# BareBones_Arduino_With_Multiplexer.net
KiCad netlist of a schematic drawn in EAGLE
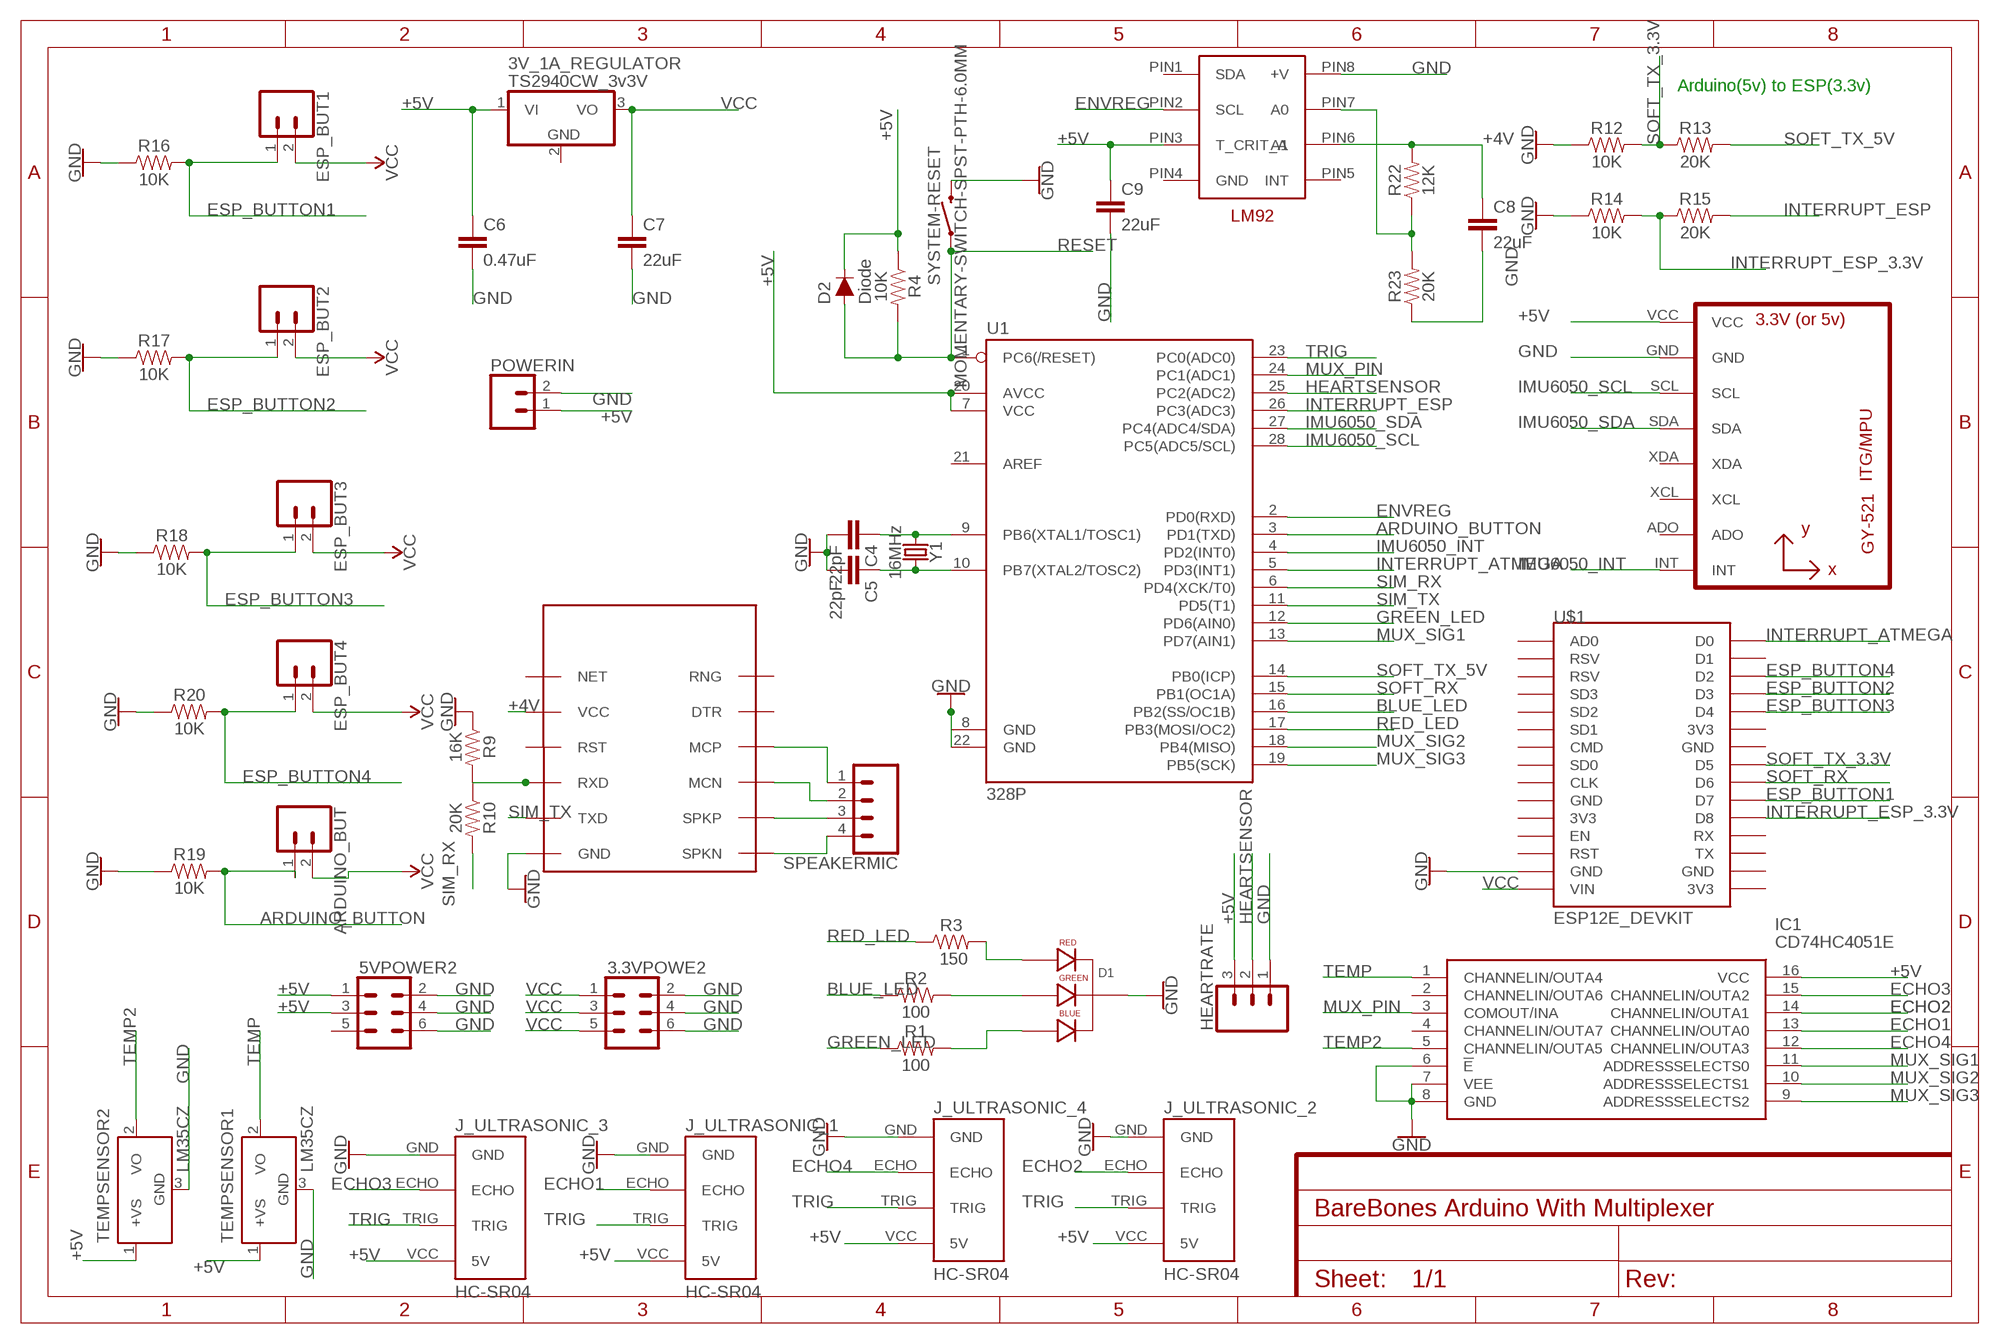
[diagram p0: schematic, sheet 1]

(export (version "E")
  (design (tool "Eeschema 10.0.6"))
  (components
    (comp (ref "3.3VPOWE2")
      (value "CONN_03X2FEMALE")
      (footprint "eagle-import:2X3")
      (libsource (lib "eagle-import") (part "CONN_03X2FEMALE"))
    )
    (comp (ref "3V_1A_REGULATOR")
      (value "TS2940CW_3v3V")
      (footprint "eagle-import:SOT223")
      (libsource (lib "eagle-import") (part "MCP1703DB"))
    )
    (comp (ref "5VPOWER2")
      (value "CONN_03X2FEMALE")
      (footprint "eagle-import:2X3")
      (libsource (lib "eagle-import") (part "CONN_03X2FEMALE"))
    )
    (comp (ref "ARDUINO_BUT")
      (value "CONN_02")
      (footprint "eagle-import:1X02")
      (libsource (lib "eagle-import") (part "CONN_02"))
    )
    (comp (ref "C4")
      (value "22pF")
      (footprint "eagle-import:CAP-PTH-2.54")
      (libsource (lib "eagle-import") (part "22PF-PTH-2.54MM-200V-5%"))
    )
    (comp (ref "C5")
      (value "22pF")
      (footprint "eagle-import:CAP-PTH-2.54")
      (libsource (lib "eagle-import") (part "22PF-PTH-2.54MM-200V-5%"))
    )
    (comp (ref "C6")
      (value "0.47uF")
      (footprint "eagle-import:CAP-PTH-SMALL-KIT")
      (libsource (lib "eagle-import") (part "0.1UF-KIT-EZ-50V-20%"))
    )
    (comp (ref "C7")
      (value "22uF")
      (footprint "eagle-import:CAP-PTH-SMALL-KIT")
      (libsource (lib "eagle-import") (part "0.1UF-KIT-EZ-50V-20%"))
    )
    (comp (ref "C8")
      (value "22uF")
      (footprint "eagle-import:CAP-PTH-SMALL-KIT")
      (libsource (lib "eagle-import") (part "0.1UF-KIT-EZ-50V-20%"))
    )
    (comp (ref "C9")
      (value "22uF")
      (footprint "eagle-import:CAP-PTH-SMALL-KIT")
      (libsource (lib "eagle-import") (part "0.1UF-KIT-EZ-50V-20%"))
    )
    (comp (ref "D1")
      (value "LED-RGB-CC-THRUDIFFUSE")
      (footprint "eagle-import:LED-RGB-THRU")
      (libsource (lib "eagle-import") (part "LED-RGB-CC-THRUDIFFUSE"))
    )
    (comp (ref "D2")
      (value "Diode")
      (footprint "eagle-import:DIODE-1N4148")
      (libsource (lib "eagle-import") (part "DIODE-1N4148"))
    )
    (comp (ref "ESP_BUT1")
      (value "CONN_02")
      (footprint "eagle-import:1X02")
      (libsource (lib "eagle-import") (part "CONN_02"))
    )
    (comp (ref "ESP_BUT2")
      (value "CONN_02")
      (footprint "eagle-import:1X02")
      (libsource (lib "eagle-import") (part "CONN_02"))
    )
    (comp (ref "ESP_BUT3")
      (value "CONN_02")
      (footprint "eagle-import:1X02")
      (libsource (lib "eagle-import") (part "CONN_02"))
    )
    (comp (ref "ESP_BUT4")
      (value "CONN_02")
      (footprint "eagle-import:1X02")
      (libsource (lib "eagle-import") (part "CONN_02"))
    )
    (comp (ref "HEARTRATE")
      (value "CONN_03")
      (footprint "eagle-import:1X03")
      (libsource (lib "eagle-import") (part "CONN_03"))
    )
    (comp (ref "IC1")
      (value "CD74HC4051E")
      (footprint "eagle-import:DIP794W53P254L1930H508Q16N")
      (fields (field (name "RS_PART_NUMBER") "2508240054"))
      (libsource (lib "eagle-import") (part "CD74HC4051E"))
    )
    (comp (ref "J_ULTRASONIC_1")
      (value "HC-SR04")
      (footprint "eagle-import:HC-SR04_FOOTPRINT")
      (libsource (lib "eagle-import") (part "HC-SR04"))
    )
    (comp (ref "J_ULTRASONIC_2")
      (value "HC-SR04")
      (footprint "eagle-import:HC-SR04_FOOTPRINT")
      (libsource (lib "eagle-import") (part "HC-SR04"))
    )
    (comp (ref "J_ULTRASONIC_3")
      (value "HC-SR04")
      (footprint "eagle-import:HC-SR04_FOOTPRINT")
      (libsource (lib "eagle-import") (part "HC-SR04"))
    )
    (comp (ref "J_ULTRASONIC_4")
      (value "HC-SR04")
      (footprint "eagle-import:HC-SR04_FOOTPRINT")
      (libsource (lib "eagle-import") (part "HC-SR04"))
    )
    (comp (ref "POWERIN")
      (value "CONN_025MM")
      (footprint "eagle-import:SCREWTERMINAL-5MM-2")
      (libsource (lib "eagle-import") (part "CONN_025MM"))
    )
    (comp (ref "R1")
      (value "100")
      (footprint "eagle-import:AXIAL-0.3")
      (libsource (lib "eagle-import") (part "100OHM-HORIZ-1/4W-1%"))
    )
    (comp (ref "R2")
      (value "100")
      (footprint "eagle-import:AXIAL-0.3")
      (libsource (lib "eagle-import") (part "100OHM-HORIZ-1/4W-1%"))
    )
    (comp (ref "R3")
      (value "150")
      (footprint "eagle-import:AXIAL-0.3")
      (libsource (lib "eagle-import") (part "RESISTORAXIAL-0.3"))
    )
    (comp (ref "R4")
      (value "10K")
      (footprint "eagle-import:AXIAL-0.3")
      (libsource (lib "eagle-import") (part "100OHM-HORIZ-1/4W-1%"))
    )
    (comp (ref "R9")
      (value "16K")
      (footprint "eagle-import:AXIAL-0.3")
      (libsource (lib "eagle-import") (part "100OHM-HORIZ-1/4W-1%"))
    )
    (comp (ref "R10")
      (value "20K")
      (footprint "eagle-import:AXIAL-0.3")
      (libsource (lib "eagle-import") (part "100OHM-HORIZ-1/4W-1%"))
    )
    (comp (ref "R12")
      (value "10K")
      (footprint "eagle-import:AXIAL-0.3")
      (libsource (lib "eagle-import") (part "100OHM-HORIZ-1/4W-1%"))
    )
    (comp (ref "R13")
      (value "20K")
      (footprint "eagle-import:AXIAL-0.3")
      (libsource (lib "eagle-import") (part "100OHM-HORIZ-1/4W-1%"))
    )
    (comp (ref "R14")
      (value "10K")
      (footprint "eagle-import:AXIAL-0.3")
      (libsource (lib "eagle-import") (part "100OHM-HORIZ-1/4W-1%"))
    )
    (comp (ref "R15")
      (value "20K")
      (footprint "eagle-import:AXIAL-0.3")
      (libsource (lib "eagle-import") (part "100OHM-HORIZ-1/4W-1%"))
    )
    (comp (ref "R16")
      (value "10K")
      (footprint "eagle-import:AXIAL-0.3")
      (libsource (lib "eagle-import") (part "100OHM-HORIZ-1/4W-1%"))
    )
    (comp (ref "R17")
      (value "10K")
      (footprint "eagle-import:AXIAL-0.3")
      (libsource (lib "eagle-import") (part "100OHM-HORIZ-1/4W-1%"))
    )
    (comp (ref "R18")
      (value "10K")
      (footprint "eagle-import:AXIAL-0.3")
      (libsource (lib "eagle-import") (part "100OHM-HORIZ-1/4W-1%"))
    )
    (comp (ref "R19")
      (value "10K")
      (footprint "eagle-import:AXIAL-0.3")
      (libsource (lib "eagle-import") (part "100OHM-HORIZ-1/4W-1%"))
    )
    (comp (ref "R20")
      (value "10K")
      (footprint "eagle-import:AXIAL-0.3")
      (libsource (lib "eagle-import") (part "100OHM-HORIZ-1/4W-1%"))
    )
    (comp (ref "R22")
      (value "12K")
      (footprint "eagle-import:AXIAL-0.3")
      (libsource (lib "eagle-import") (part "100OHM-HORIZ-1/4W-1%"))
    )
    (comp (ref "R23")
      (value "20K")
      (footprint "eagle-import:AXIAL-0.3")
      (libsource (lib "eagle-import") (part "100OHM-HORIZ-1/4W-1%"))
    )
    (comp (ref "SPEAKERMIC")
      (value "CONN_04")
      (footprint "eagle-import:1X04")
      (libsource (lib "eagle-import") (part "CONN_04"))
    )
    (comp (ref "SYSTEM-RESET")
      (value "MOMENTARY-SWITCH-SPST-PTH-6.0MM")
      (footprint "eagle-import:TACTILE_SWITCH_PTH_6.0MM")
      (libsource (lib "eagle-import") (part "MOMENTARY-SWITCH-SPST-PTH-6.0MM"))
    )
    (comp (ref "TEMPSENSOR1")
      (value "LM35CZ")
      (footprint "eagle-import:TO92")
      (libsource (lib "eagle-import") (part "LM35CZ"))
    )
    (comp (ref "TEMPSENSOR2")
      (value "LM35CZ")
      (footprint "eagle-import:TO92")
      (libsource (lib "eagle-import") (part "LM35CZ"))
    )
    (comp (ref "U$1")
      (value "ESP12E_DEVKIT")
      (footprint "eagle-import:ESP12E_DEVKIT")
      (libsource (lib "eagle-import") (part "ESP12E_DEVKIT"))
    )
    (comp (ref "U$4")
      (value "SIM800L")
      (footprint "eagle-import:SIM-CORE")
      (libsource (lib "eagle-import") (part "SIM800L"))
    )
    (comp (ref "U1")
      (value "328P")
      (footprint "eagle-import:DIP28")
      (libsource (lib "eagle-import") (part "ATMEGA328P_PDIP"))
    )
    (comp (ref "U2")
      (value "GY-521MPU6050")
      (footprint "eagle-import:GY-521")
      (libsource (lib "eagle-import") (part "GY-521MPU6050"))
    )
    (comp (ref "VREG")
      (value "LM92")
      (footprint "eagle-import:SOP-8")
      (fields (field (name "SPICEPREFIX") "X"))
      (libsource (lib "eagle-import") (part "LM92"))
    )
    (comp (ref "Y1")
      (value "16MHz")
      (footprint "eagle-import:HC49US")
      (libsource (lib "eagle-import") (part "CRYSTAL-16MHZPTH-HC49US"))
    )
  )
  (nets
    (net (code "1") (name "/+4V") (class "Default")
      (node (ref "C8") (pin "1") (pinfunction "1_1") (pintype "passive"))
      (node (ref "R22") (pin "P$2") (pinfunction "2_P$2") (pintype "passive"))
      (node (ref "U$4") (pin "VCC") (pinfunction "VCC_VCC") (pintype "bidirectional"))
      (node (ref "VREG") (pin "PIN6") (pinfunction "A1_PIN6") (pintype "bidirectional"))
    )
    (net (code "2") (name "/+5V") (class "Default")
      (node (ref "3V_1A_REGULATOR") (pin "1") (pinfunction "VI_1") (pintype "input"))
      (node (ref "5VPOWER2") (pin "1") (pinfunction "1_1") (pintype "bidirectional"))
      (node (ref "5VPOWER2") (pin "3") (pinfunction "3_3") (pintype "bidirectional"))
      (node (ref "C6") (pin "1") (pinfunction "1_1") (pintype "passive"))
      (node (ref "C9") (pin "1") (pinfunction "1_1") (pintype "passive"))
      (node (ref "D2") (pin "C") (pinfunction "C_C") (pintype "passive"))
      (node (ref "HEARTRATE") (pin "3") (pinfunction "3_3") (pintype "passive"))
      (node (ref "IC1") (pin "16") (pinfunction "VCC_16") (pintype "input"))
      (node (ref "J_ULTRASONIC_1") (pin "VCC") (pinfunction "5V_VCC") (pintype "bidirectional"))
      (node (ref "J_ULTRASONIC_2") (pin "VCC") (pinfunction "5V_VCC") (pintype "bidirectional"))
      (node (ref "J_ULTRASONIC_3") (pin "VCC") (pinfunction "5V_VCC") (pintype "bidirectional"))
      (node (ref "J_ULTRASONIC_4") (pin "VCC") (pinfunction "5V_VCC") (pintype "bidirectional"))
      (node (ref "POWERIN") (pin "1") (pinfunction "1_1") (pintype "passive"))
      (node (ref "R4") (pin "P$1") (pinfunction "1_P$1") (pintype "passive"))
      (node (ref "TEMPSENSOR1") (pin "1") (pinfunction "+VS_1") (pintype "input"))
      (node (ref "TEMPSENSOR2") (pin "1") (pinfunction "+VS_1") (pintype "input"))
      (node (ref "U1") (pin "20") (pinfunction "AVCC_20") (pintype "bidirectional"))
      (node (ref "U1") (pin "7") (pinfunction "VCC_7") (pintype "bidirectional"))
      (node (ref "U2") (pin "VCC") (pinfunction "VCC_VCC") (pintype "bidirectional"))
      (node (ref "VREG") (pin "PIN3") (pinfunction "T_CRIT_A_PIN3") (pintype "bidirectional"))
    )
    (net (code "3") (name "/ARDUINO_BUTTON") (class "Default")
      (node (ref "ARDUINO_BUT") (pin "1") (pinfunction "1_1") (pintype "passive"))
      (node (ref "R19") (pin "P$2") (pinfunction "2_P$2") (pintype "passive"))
      (node (ref "U1") (pin "3") (pinfunction "PD1(TXD)_3") (pintype "bidirectional"))
    )
    (net (code "4") (name "/BLUE_LED") (class "Default")
      (node (ref "R2") (pin "P$1") (pinfunction "1_P$1") (pintype "passive"))
      (node (ref "U1") (pin "16") (pinfunction "PB2(SS/OC1B)_16") (pintype "bidirectional"))
    )
    (net (code "5") (name "/ECHO1") (class "Default")
      (node (ref "IC1") (pin "13") (pinfunction "CHANNELIN/OUTA0_13") (pintype "input"))
      (node (ref "J_ULTRASONIC_1") (pin "ECHO") (pinfunction "ECHO_ECHO") (pintype "bidirectional"))
    )
    (net (code "6") (name "/ECHO2") (class "Default")
      (node (ref "IC1") (pin "14") (pinfunction "CHANNELIN/OUTA1_14") (pintype "input"))
      (node (ref "J_ULTRASONIC_2") (pin "ECHO") (pinfunction "ECHO_ECHO") (pintype "bidirectional"))
    )
    (net (code "7") (name "/ECHO3") (class "Default")
      (node (ref "IC1") (pin "15") (pinfunction "CHANNELIN/OUTA2_15") (pintype "input"))
      (node (ref "J_ULTRASONIC_3") (pin "ECHO") (pinfunction "ECHO_ECHO") (pintype "bidirectional"))
    )
    (net (code "8") (name "/ECHO4") (class "Default")
      (node (ref "IC1") (pin "12") (pinfunction "CHANNELIN/OUTA3_12") (pintype "input"))
      (node (ref "J_ULTRASONIC_4") (pin "ECHO") (pinfunction "ECHO_ECHO") (pintype "bidirectional"))
    )
    (net (code "9") (name "/ENVREG") (class "Default")
      (node (ref "U1") (pin "2") (pinfunction "PD0(RXD)_2") (pintype "bidirectional"))
      (node (ref "VREG") (pin "PIN2") (pinfunction "SCL_PIN2") (pintype "bidirectional"))
    )
    (net (code "10") (name "/ESP_BUTTON1") (class "Default")
      (node (ref "ESP_BUT1") (pin "1") (pinfunction "1_1") (pintype "passive"))
      (node (ref "R16") (pin "P$2") (pinfunction "2_P$2") (pintype "passive"))
      (node (ref "U$1") (pin "D7") (pinfunction "D7_D7") (pintype "bidirectional"))
    )
    (net (code "11") (name "/ESP_BUTTON2") (class "Default")
      (node (ref "ESP_BUT2") (pin "1") (pinfunction "1_1") (pintype "passive"))
      (node (ref "R17") (pin "P$2") (pinfunction "2_P$2") (pintype "passive"))
      (node (ref "U$1") (pin "D3") (pinfunction "D3_D3") (pintype "bidirectional"))
    )
    (net (code "12") (name "/ESP_BUTTON3") (class "Default")
      (node (ref "ESP_BUT3") (pin "1") (pinfunction "1_1") (pintype "passive"))
      (node (ref "R18") (pin "P$2") (pinfunction "2_P$2") (pintype "passive"))
      (node (ref "U$1") (pin "D4") (pinfunction "D4_D4") (pintype "bidirectional"))
    )
    (net (code "13") (name "/ESP_BUTTON4") (class "Default")
      (node (ref "ESP_BUT4") (pin "1") (pinfunction "1_1") (pintype "passive"))
      (node (ref "R20") (pin "P$2") (pinfunction "2_P$2") (pintype "passive"))
      (node (ref "U$1") (pin "D2") (pinfunction "D2_D2") (pintype "bidirectional"))
    )
    (net (code "14") (name "/GREEN_LED") (class "Default")
      (node (ref "R1") (pin "P$1") (pinfunction "1_P$1") (pintype "passive"))
      (node (ref "U1") (pin "12") (pinfunction "PD6(AIN0)_12") (pintype "bidirectional"))
    )
    (net (code "15") (name "/HEARTSENSOR") (class "Default")
      (node (ref "HEARTRATE") (pin "2") (pinfunction "2_2") (pintype "passive"))
      (node (ref "U1") (pin "25") (pinfunction "PC2(ADC2)_25") (pintype "bidirectional"))
    )
    (net (code "16") (name "/IMU6050_INT") (class "Default")
      (node (ref "U1") (pin "4") (pinfunction "PD2(INT0)_4") (pintype "bidirectional"))
      (node (ref "U2") (pin "INT") (pinfunction "INT_INT") (pintype "bidirectional"))
    )
    (net (code "17") (name "/IMU6050_SCL") (class "Default")
      (node (ref "U1") (pin "28") (pinfunction "PC5(ADC5/SCL)_28") (pintype "bidirectional"))
      (node (ref "U2") (pin "SCL") (pinfunction "SCL_SCL") (pintype "bidirectional"))
    )
    (net (code "18") (name "/IMU6050_SDA") (class "Default")
      (node (ref "U1") (pin "27") (pinfunction "PC4(ADC4/SDA)_27") (pintype "bidirectional"))
      (node (ref "U2") (pin "SDA") (pinfunction "SDA_SDA") (pintype "bidirectional"))
    )
    (net (code "19") (name "/INTERRUPT_ATMEGA") (class "Default")
      (node (ref "U$1") (pin "D0") (pinfunction "D0_D0") (pintype "bidirectional"))
      (node (ref "U1") (pin "5") (pinfunction "PD3(INT1)_5") (pintype "bidirectional"))
    )
    (net (code "20") (name "/INTERRUPT_ESP") (class "Default")
      (node (ref "R15") (pin "P$2") (pinfunction "2_P$2") (pintype "passive"))
      (node (ref "U1") (pin "26") (pinfunction "PC3(ADC3)_26") (pintype "bidirectional"))
    )
    (net (code "21") (name "/INTERRUPT_ESP_3.3V") (class "Default")
      (node (ref "R14") (pin "P$2") (pinfunction "2_P$2") (pintype "passive"))
      (node (ref "R15") (pin "P$1") (pinfunction "1_P$1") (pintype "passive"))
      (node (ref "U$1") (pin "D8") (pinfunction "D8_D8") (pintype "bidirectional"))
    )
    (net (code "22") (name "/MUX_PIN") (class "Default")
      (node (ref "IC1") (pin "3") (pinfunction "COMOUT/INA_3") (pintype "input"))
      (node (ref "U1") (pin "24") (pinfunction "PC1(ADC1)_24") (pintype "bidirectional"))
    )
    (net (code "23") (name "/MUX_SIG1") (class "Default")
      (node (ref "IC1") (pin "11") (pinfunction "ADDRESSSELECTS0_11") (pintype "input"))
      (node (ref "U1") (pin "13") (pinfunction "PD7(AIN1)_13") (pintype "bidirectional"))
    )
    (net (code "24") (name "/MUX_SIG2") (class "Default")
      (node (ref "IC1") (pin "10") (pinfunction "ADDRESSSELECTS1_10") (pintype "input"))
      (node (ref "U1") (pin "18") (pinfunction "PB4(MISO)_18") (pintype "bidirectional"))
    )
    (net (code "25") (name "/MUX_SIG3") (class "Default")
      (node (ref "IC1") (pin "9") (pinfunction "ADDRESSSELECTS2_9") (pintype "input"))
      (node (ref "U1") (pin "19") (pinfunction "PB5(SCK)_19") (pintype "bidirectional"))
    )
    (net (code "26") (name "/RED_LED") (class "Default")
      (node (ref "R3") (pin "P$1") (pinfunction "1_P$1") (pintype "passive"))
      (node (ref "U1") (pin "17") (pinfunction "PB3(MOSI/OC2)_17") (pintype "bidirectional"))
    )
    (net (code "27") (name "/RESET") (class "Default")
      (node (ref "D2") (pin "A") (pinfunction "A_A") (pintype "passive"))
      (node (ref "R4") (pin "P$2") (pinfunction "2_P$2") (pintype "passive"))
      (node (ref "SYSTEM-RESET") (pin "1") (pinfunction "1_1") (pintype "passive"))
      (node (ref "U1") (pin "1") (pinfunction "PC6(/RESET)_1") (pintype "bidirectional"))
    )
    (net (code "28") (name "/SIM_RX") (class "Default")
      (node (ref "R10") (pin "P$2") (pinfunction "2_P$2") (pintype "passive"))
      (node (ref "U1") (pin "6") (pinfunction "PD4(XCK/T0)_6") (pintype "bidirectional"))
    )
    (net (code "29") (name "/SIM_TX") (class "Default")
      (node (ref "U$4") (pin "TXD") (pinfunction "TXD_TXD") (pintype "bidirectional"))
      (node (ref "U1") (pin "11") (pinfunction "PD5(T1)_11") (pintype "bidirectional"))
    )
    (net (code "30") (name "/SOFT_RX") (class "Default")
      (node (ref "U$1") (pin "D6") (pinfunction "D6_D6") (pintype "bidirectional"))
      (node (ref "U1") (pin "15") (pinfunction "PB1(OC1A)_15") (pintype "bidirectional"))
    )
    (net (code "31") (name "/SOFT_TX_3.3V") (class "Default")
      (node (ref "R12") (pin "P$2") (pinfunction "2_P$2") (pintype "passive"))
      (node (ref "R13") (pin "P$1") (pinfunction "1_P$1") (pintype "passive"))
      (node (ref "U$1") (pin "D5") (pinfunction "D5_D5") (pintype "bidirectional"))
    )
    (net (code "32") (name "/SOFT_TX_5V") (class "Default")
      (node (ref "R13") (pin "P$2") (pinfunction "2_P$2") (pintype "passive"))
      (node (ref "U1") (pin "14") (pinfunction "PB0(ICP)_14") (pintype "bidirectional"))
    )
    (net (code "33") (name "/TEMP") (class "Default")
      (node (ref "IC1") (pin "1") (pinfunction "CHANNELIN/OUTA4_1") (pintype "input"))
      (node (ref "TEMPSENSOR1") (pin "2") (pinfunction "VO_2") (pintype "input"))
    )
    (net (code "34") (name "/TEMP2") (class "Default")
      (node (ref "IC1") (pin "5") (pinfunction "CHANNELIN/OUTA5_5") (pintype "input"))
      (node (ref "TEMPSENSOR2") (pin "2") (pinfunction "VO_2") (pintype "input"))
    )
    (net (code "35") (name "/TRIG") (class "Default")
      (node (ref "J_ULTRASONIC_1") (pin "TRIG") (pinfunction "TRIG_TRIG") (pintype "bidirectional"))
      (node (ref "J_ULTRASONIC_2") (pin "TRIG") (pinfunction "TRIG_TRIG") (pintype "bidirectional"))
      (node (ref "J_ULTRASONIC_3") (pin "TRIG") (pinfunction "TRIG_TRIG") (pintype "bidirectional"))
      (node (ref "J_ULTRASONIC_4") (pin "TRIG") (pinfunction "TRIG_TRIG") (pintype "bidirectional"))
      (node (ref "U1") (pin "23") (pinfunction "PC0(ADC0)_23") (pintype "bidirectional"))
    )
    (net (code "36") (name "GND") (class "Default")
      (node (ref "3.3VPOWE2") (pin "2") (pinfunction "2_2") (pintype "bidirectional"))
      (node (ref "3.3VPOWE2") (pin "4") (pinfunction "4_4") (pintype "bidirectional"))
      (node (ref "3.3VPOWE2") (pin "6") (pinfunction "6_6") (pintype "bidirectional"))
      (node (ref "5VPOWER2") (pin "2") (pinfunction "2_2") (pintype "bidirectional"))
      (node (ref "5VPOWER2") (pin "4") (pinfunction "4_4") (pintype "bidirectional"))
      (node (ref "5VPOWER2") (pin "6") (pinfunction "6_6") (pintype "bidirectional"))
      (node (ref "C4") (pin "2") (pinfunction "2_2") (pintype "passive"))
      (node (ref "C5") (pin "2") (pinfunction "2_2") (pintype "passive"))
      (node (ref "C6") (pin "2") (pinfunction "2_2") (pintype "passive"))
      (node (ref "C7") (pin "2") (pinfunction "2_2") (pintype "passive"))
      (node (ref "C8") (pin "2") (pinfunction "2_2") (pintype "passive"))
      (node (ref "C9") (pin "2") (pinfunction "2_2") (pintype "passive"))
      (node (ref "D1") (pin "2") (pinfunction "CATHODE_2") (pintype "bidirectional"))
      (node (ref "HEARTRATE") (pin "1") (pinfunction "1_1") (pintype "passive"))
      (node (ref "IC1") (pin "6") (pinfunction "~{E}_6") (pintype "input"))
      (node (ref "IC1") (pin "7") (pinfunction "VEE_7") (pintype "input"))
      (node (ref "IC1") (pin "8") (pinfunction "GND_8") (pintype "input"))
      (node (ref "J_ULTRASONIC_1") (pin "GND") (pinfunction "GND_GND") (pintype "bidirectional"))
      (node (ref "J_ULTRASONIC_2") (pin "GND") (pinfunction "GND_GND") (pintype "bidirectional"))
      (node (ref "J_ULTRASONIC_3") (pin "GND") (pinfunction "GND_GND") (pintype "bidirectional"))
      (node (ref "J_ULTRASONIC_4") (pin "GND") (pinfunction "GND_GND") (pintype "bidirectional"))
      (node (ref "POWERIN") (pin "2") (pinfunction "2_2") (pintype "passive"))
      (node (ref "R12") (pin "P$1") (pinfunction "1_P$1") (pintype "passive"))
      (node (ref "R14") (pin "P$1") (pinfunction "1_P$1") (pintype "passive"))
      (node (ref "R16") (pin "P$1") (pinfunction "1_P$1") (pintype "passive"))
      (node (ref "R17") (pin "P$1") (pinfunction "1_P$1") (pintype "passive"))
      (node (ref "R18") (pin "P$1") (pinfunction "1_P$1") (pintype "passive"))
      (node (ref "R19") (pin "P$1") (pinfunction "1_P$1") (pintype "passive"))
      (node (ref "R20") (pin "P$1") (pinfunction "1_P$1") (pintype "passive"))
      (node (ref "R23") (pin "P$1") (pinfunction "1_P$1") (pintype "passive"))
      (node (ref "R9") (pin "P$1") (pinfunction "1_P$1") (pintype "passive"))
      (node (ref "SYSTEM-RESET") (pin "3") (pinfunction "2_3") (pintype "passive"))
      (node (ref "TEMPSENSOR1") (pin "3") (pinfunction "GND_3") (pintype "power_in"))
      (node (ref "TEMPSENSOR2") (pin "3") (pinfunction "GND_3") (pintype "power_in"))
      (node (ref "U$1") (pin "GND@1") (pinfunction "GND_GND@1") (pintype "bidirectional"))
      (node (ref "U$4") (pin "GND") (pinfunction "GND_GND") (pintype "bidirectional"))
      (node (ref "U1") (pin "22") (pinfunction "GND_22") (pintype "bidirectional"))
      (node (ref "U1") (pin "8") (pinfunction "GND_8") (pintype "bidirectional"))
      (node (ref "U2") (pin "GND") (pinfunction "GND_GND") (pintype "bidirectional"))
      (node (ref "VREG") (pin "PIN8") (pinfunction "+V_PIN8") (pintype "bidirectional"))
    )
    (net (code "37") (name "Net-(D1-BLUE_CATHODE)") (class "Default")
      (node (ref "D1") (pin "4") (pinfunction "BLUE_CATHODE_4") (pintype "bidirectional"))
      (node (ref "R1") (pin "P$2") (pinfunction "2_P$2") (pintype "passive"))
    )
    (net (code "38") (name "Net-(D1-GREEN_CATHODE)") (class "Default")
      (node (ref "D1") (pin "3") (pinfunction "GREEN_CATHODE_3") (pintype "bidirectional"))
      (node (ref "R2") (pin "P$2") (pinfunction "2_P$2") (pintype "passive"))
    )
    (net (code "39") (name "Net-(D1-RED_CATHODE)") (class "Default")
      (node (ref "D1") (pin "1") (pinfunction "RED_CATHODE_1") (pintype "bidirectional"))
      (node (ref "R3") (pin "P$2") (pinfunction "2_P$2") (pintype "passive"))
    )
    (net (code "40") (name "Net-(R10-1)") (class "Default")
      (node (ref "R10") (pin "P$1") (pinfunction "1_P$1") (pintype "passive"))
      (node (ref "R9") (pin "P$2") (pinfunction "2_P$2") (pintype "passive"))
      (node (ref "U$4") (pin "RXD") (pinfunction "RXD_RXD") (pintype "bidirectional"))
    )
    (net (code "41") (name "Net-(R22-1)") (class "Default")
      (node (ref "R22") (pin "P$1") (pinfunction "1_P$1") (pintype "passive"))
      (node (ref "R23") (pin "P$2") (pinfunction "2_P$2") (pintype "passive"))
      (node (ref "VREG") (pin "PIN7") (pinfunction "A0_PIN7") (pintype "bidirectional"))
    )
    (net (code "42") (name "Net-(SPEAKERMIC-Pad1)") (class "Default")
      (node (ref "SPEAKERMIC") (pin "1") (pinfunction "1_1") (pintype "passive"))
      (node (ref "U$4") (pin "MCP") (pinfunction "MCP_MCP") (pintype "bidirectional"))
    )
    (net (code "43") (name "Net-(SPEAKERMIC-Pad2)") (class "Default")
      (node (ref "SPEAKERMIC") (pin "2") (pinfunction "2_2") (pintype "passive"))
      (node (ref "U$4") (pin "MCN") (pinfunction "MCN_MCN") (pintype "bidirectional"))
    )
    (net (code "44") (name "Net-(SPEAKERMIC-Pad3)") (class "Default")
      (node (ref "SPEAKERMIC") (pin "3") (pinfunction "3_3") (pintype "passive"))
      (node (ref "U$4") (pin "SPKP") (pinfunction "SPKP_SPKP") (pintype "bidirectional"))
    )
    (net (code "45") (name "Net-(SPEAKERMIC-Pad4)") (class "Default")
      (node (ref "SPEAKERMIC") (pin "4") (pinfunction "4_4") (pintype "passive"))
      (node (ref "U$4") (pin "SPKN") (pinfunction "SPKN_SPKN") (pintype "bidirectional"))
    )
    (net (code "46") (name "Net-(U1-PB6(XTAL1{slash}TOSC1))") (class "Default")
      (node (ref "C4") (pin "1") (pinfunction "1_1") (pintype "passive"))
      (node (ref "U1") (pin "9") (pinfunction "PB6(XTAL1/TOSC1)_9") (pintype "bidirectional"))
      (node (ref "Y1") (pin "1") (pinfunction "1_1") (pintype "passive"))
    )
    (net (code "47") (name "Net-(U1-PB7(XTAL2{slash}TOSC2))") (class "Default")
      (node (ref "C5") (pin "1") (pinfunction "1_1") (pintype "passive"))
      (node (ref "U1") (pin "10") (pinfunction "PB7(XTAL2/TOSC2)_10") (pintype "bidirectional"))
      (node (ref "Y1") (pin "2") (pinfunction "2_2") (pintype "passive"))
    )
    (net (code "48") (name "VCC") (class "Default")
      (node (ref "3.3VPOWE2") (pin "1") (pinfunction "1_1") (pintype "bidirectional"))
      (node (ref "3.3VPOWE2") (pin "3") (pinfunction "3_3") (pintype "bidirectional"))
      (node (ref "3.3VPOWE2") (pin "5") (pinfunction "5_5") (pintype "bidirectional"))
      (node (ref "3V_1A_REGULATOR") (pin "3") (pinfunction "VO_3") (pintype "passive"))
      (node (ref "ARDUINO_BUT") (pin "2") (pinfunction "2_2") (pintype "passive"))
      (node (ref "C7") (pin "1") (pinfunction "1_1") (pintype "passive"))
      (node (ref "ESP_BUT1") (pin "2") (pinfunction "2_2") (pintype "passive"))
      (node (ref "ESP_BUT2") (pin "2") (pinfunction "2_2") (pintype "passive"))
      (node (ref "ESP_BUT3") (pin "2") (pinfunction "2_2") (pintype "passive"))
      (node (ref "ESP_BUT4") (pin "2") (pinfunction "2_2") (pintype "passive"))
      (node (ref "U$1") (pin "VIN") (pinfunction "VIN_VIN") (pintype "bidirectional"))
    )
    (net (code "49") (name "unconnected-(3V_1A_REGULATOR-GND-Pad2)") (class "Default")
      (node (ref "3V_1A_REGULATOR") (pin "2") (pinfunction "GND_2") (pintype "passive"))
    )
    (net (code "50") (name "unconnected-(5VPOWER2-Pad5)") (class "Default")
      (node (ref "5VPOWER2") (pin "5") (pinfunction "5_5") (pintype "bidirectional"))
    )
    (net (code "51") (name "unconnected-(IC1-CHANNELIN{slash}OUTA6-Pad2)") (class "Default")
      (node (ref "IC1") (pin "2") (pinfunction "CHANNELIN/OUTA6_2") (pintype "input"))
    )
    (net (code "52") (name "unconnected-(IC1-CHANNELIN{slash}OUTA7-Pad4)") (class "Default")
      (node (ref "IC1") (pin "4") (pinfunction "CHANNELIN/OUTA7_4") (pintype "input"))
    )
    (net (code "53") (name "unconnected-(U$1-3V3-Pad3V3@0)") (class "Default")
      (node (ref "U$1") (pin "3V3@0") (pinfunction "3V3_3V3@0") (pintype "bidirectional"))
    )
    (net (code "54") (name "unconnected-(U$1-3V3-Pad3V3@1)") (class "Default")
      (node (ref "U$1") (pin "3V3@1") (pinfunction "3V3_3V3@1") (pintype "bidirectional"))
    )
    (net (code "55") (name "unconnected-(U$1-3V3-Pad3V3@2)") (class "Default")
      (node (ref "U$1") (pin "3V3@2") (pinfunction "3V3_3V3@2") (pintype "bidirectional"))
    )
    (net (code "56") (name "unconnected-(U$1-GND-PadGND@0)") (class "Default")
      (node (ref "U$1") (pin "GND@0") (pinfunction "GND_GND@0") (pintype "bidirectional"))
    )
    (net (code "57") (name "unconnected-(U$1-GND-PadGND@2)") (class "Default")
      (node (ref "U$1") (pin "GND@2") (pinfunction "GND_GND@2") (pintype "bidirectional"))
    )
    (net (code "58") (name "unconnected-(U$1-GND-PadGND@3)") (class "Default")
      (node (ref "U$1") (pin "GND@3") (pinfunction "GND_GND@3") (pintype "bidirectional"))
    )
    (net (code "59") (name "unconnected-(U$1-PadAD0)") (class "Default")
      (node (ref "U$1") (pin "AD0") (pinfunction "AD0_AD0") (pintype "bidirectional"))
    )
    (net (code "60") (name "unconnected-(U$1-PadCLK)") (class "Default")
      (node (ref "U$1") (pin "CLK") (pinfunction "CLK_CLK") (pintype "bidirectional"))
    )
    (net (code "61") (name "unconnected-(U$1-PadCMD)") (class "Default")
      (node (ref "U$1") (pin "CMD") (pinfunction "CMD_CMD") (pintype "bidirectional"))
    )
    (net (code "62") (name "unconnected-(U$1-PadD1)") (class "Default")
      (node (ref "U$1") (pin "D1") (pinfunction "D1_D1") (pintype "bidirectional"))
    )
    (net (code "63") (name "unconnected-(U$1-PadEN)") (class "Default")
      (node (ref "U$1") (pin "EN") (pinfunction "EN_EN") (pintype "bidirectional"))
    )
    (net (code "64") (name "unconnected-(U$1-PadRST)") (class "Default")
      (node (ref "U$1") (pin "RST") (pinfunction "RST_RST") (pintype "bidirectional"))
    )
    (net (code "65") (name "unconnected-(U$1-PadRX)") (class "Default")
      (node (ref "U$1") (pin "RX") (pinfunction "RX_RX") (pintype "bidirectional"))
    )
    (net (code "66") (name "unconnected-(U$1-PadSD0)") (class "Default")
      (node (ref "U$1") (pin "SD0") (pinfunction "SD0_SD0") (pintype "bidirectional"))
    )
    (net (code "67") (name "unconnected-(U$1-PadSD1)") (class "Default")
      (node (ref "U$1") (pin "SD1") (pinfunction "SD1_SD1") (pintype "bidirectional"))
    )
    (net (code "68") (name "unconnected-(U$1-PadSD2)") (class "Default")
      (node (ref "U$1") (pin "SD2") (pinfunction "SD2_SD2") (pintype "bidirectional"))
    )
    (net (code "69") (name "unconnected-(U$1-PadSD3)") (class "Default")
      (node (ref "U$1") (pin "SD3") (pinfunction "SD3_SD3") (pintype "bidirectional"))
    )
    (net (code "70") (name "unconnected-(U$1-PadTX)") (class "Default")
      (node (ref "U$1") (pin "TX") (pinfunction "TX_TX") (pintype "bidirectional"))
    )
    (net (code "71") (name "unconnected-(U$1-RSV-PadRSV@0)") (class "Default")
      (node (ref "U$1") (pin "RSV@0") (pinfunction "RSV_RSV@0") (pintype "bidirectional"))
    )
    (net (code "72") (name "unconnected-(U$1-RSV-PadRSV@1)") (class "Default")
      (node (ref "U$1") (pin "RSV@1") (pinfunction "RSV_RSV@1") (pintype "bidirectional"))
    )
    (net (code "73") (name "unconnected-(U$4-PadDTR)") (class "Default")
      (node (ref "U$4") (pin "DTR") (pinfunction "DTR_DTR") (pintype "bidirectional"))
    )
    (net (code "74") (name "unconnected-(U$4-PadNET)") (class "Default")
      (node (ref "U$4") (pin "NET") (pinfunction "NET_NET") (pintype "bidirectional"))
    )
    (net (code "75") (name "unconnected-(U$4-PadRNG)") (class "Default")
      (node (ref "U$4") (pin "RNG") (pinfunction "RNG_RNG") (pintype "bidirectional"))
    )
    (net (code "76") (name "unconnected-(U$4-PadRST)") (class "Default")
      (node (ref "U$4") (pin "RST") (pinfunction "RST_RST") (pintype "bidirectional"))
    )
    (net (code "77") (name "unconnected-(U1-AREF-Pad21)") (class "Default")
      (node (ref "U1") (pin "21") (pinfunction "AREF_21") (pintype "bidirectional"))
    )
    (net (code "78") (name "unconnected-(U2-PadADO)") (class "Default")
      (node (ref "U2") (pin "ADO") (pinfunction "ADO_ADO") (pintype "bidirectional"))
    )
    (net (code "79") (name "unconnected-(U2-PadXCL)") (class "Default")
      (node (ref "U2") (pin "XCL") (pinfunction "XCL_XCL") (pintype "bidirectional"))
    )
    (net (code "80") (name "unconnected-(U2-PadXDA)") (class "Default")
      (node (ref "U2") (pin "XDA") (pinfunction "XDA_XDA") (pintype "bidirectional"))
    )
    (net (code "81") (name "unconnected-(VREG-GND-PadPIN4)") (class "Default")
      (node (ref "VREG") (pin "PIN4") (pinfunction "GND_PIN4") (pintype "bidirectional"))
    )
    (net (code "82") (name "unconnected-(VREG-INT-PadPIN5)") (class "Default")
      (node (ref "VREG") (pin "PIN5") (pinfunction "INT_PIN5") (pintype "bidirectional"))
    )
    (net (code "83") (name "unconnected-(VREG-SDA-PadPIN1)") (class "Default")
      (node (ref "VREG") (pin "PIN1") (pinfunction "SDA_PIN1") (pintype "bidirectional"))
    )
  )
)
